# CAN_IB_V1.net
KiCad netlist of a schematic drawn in Altium Designer
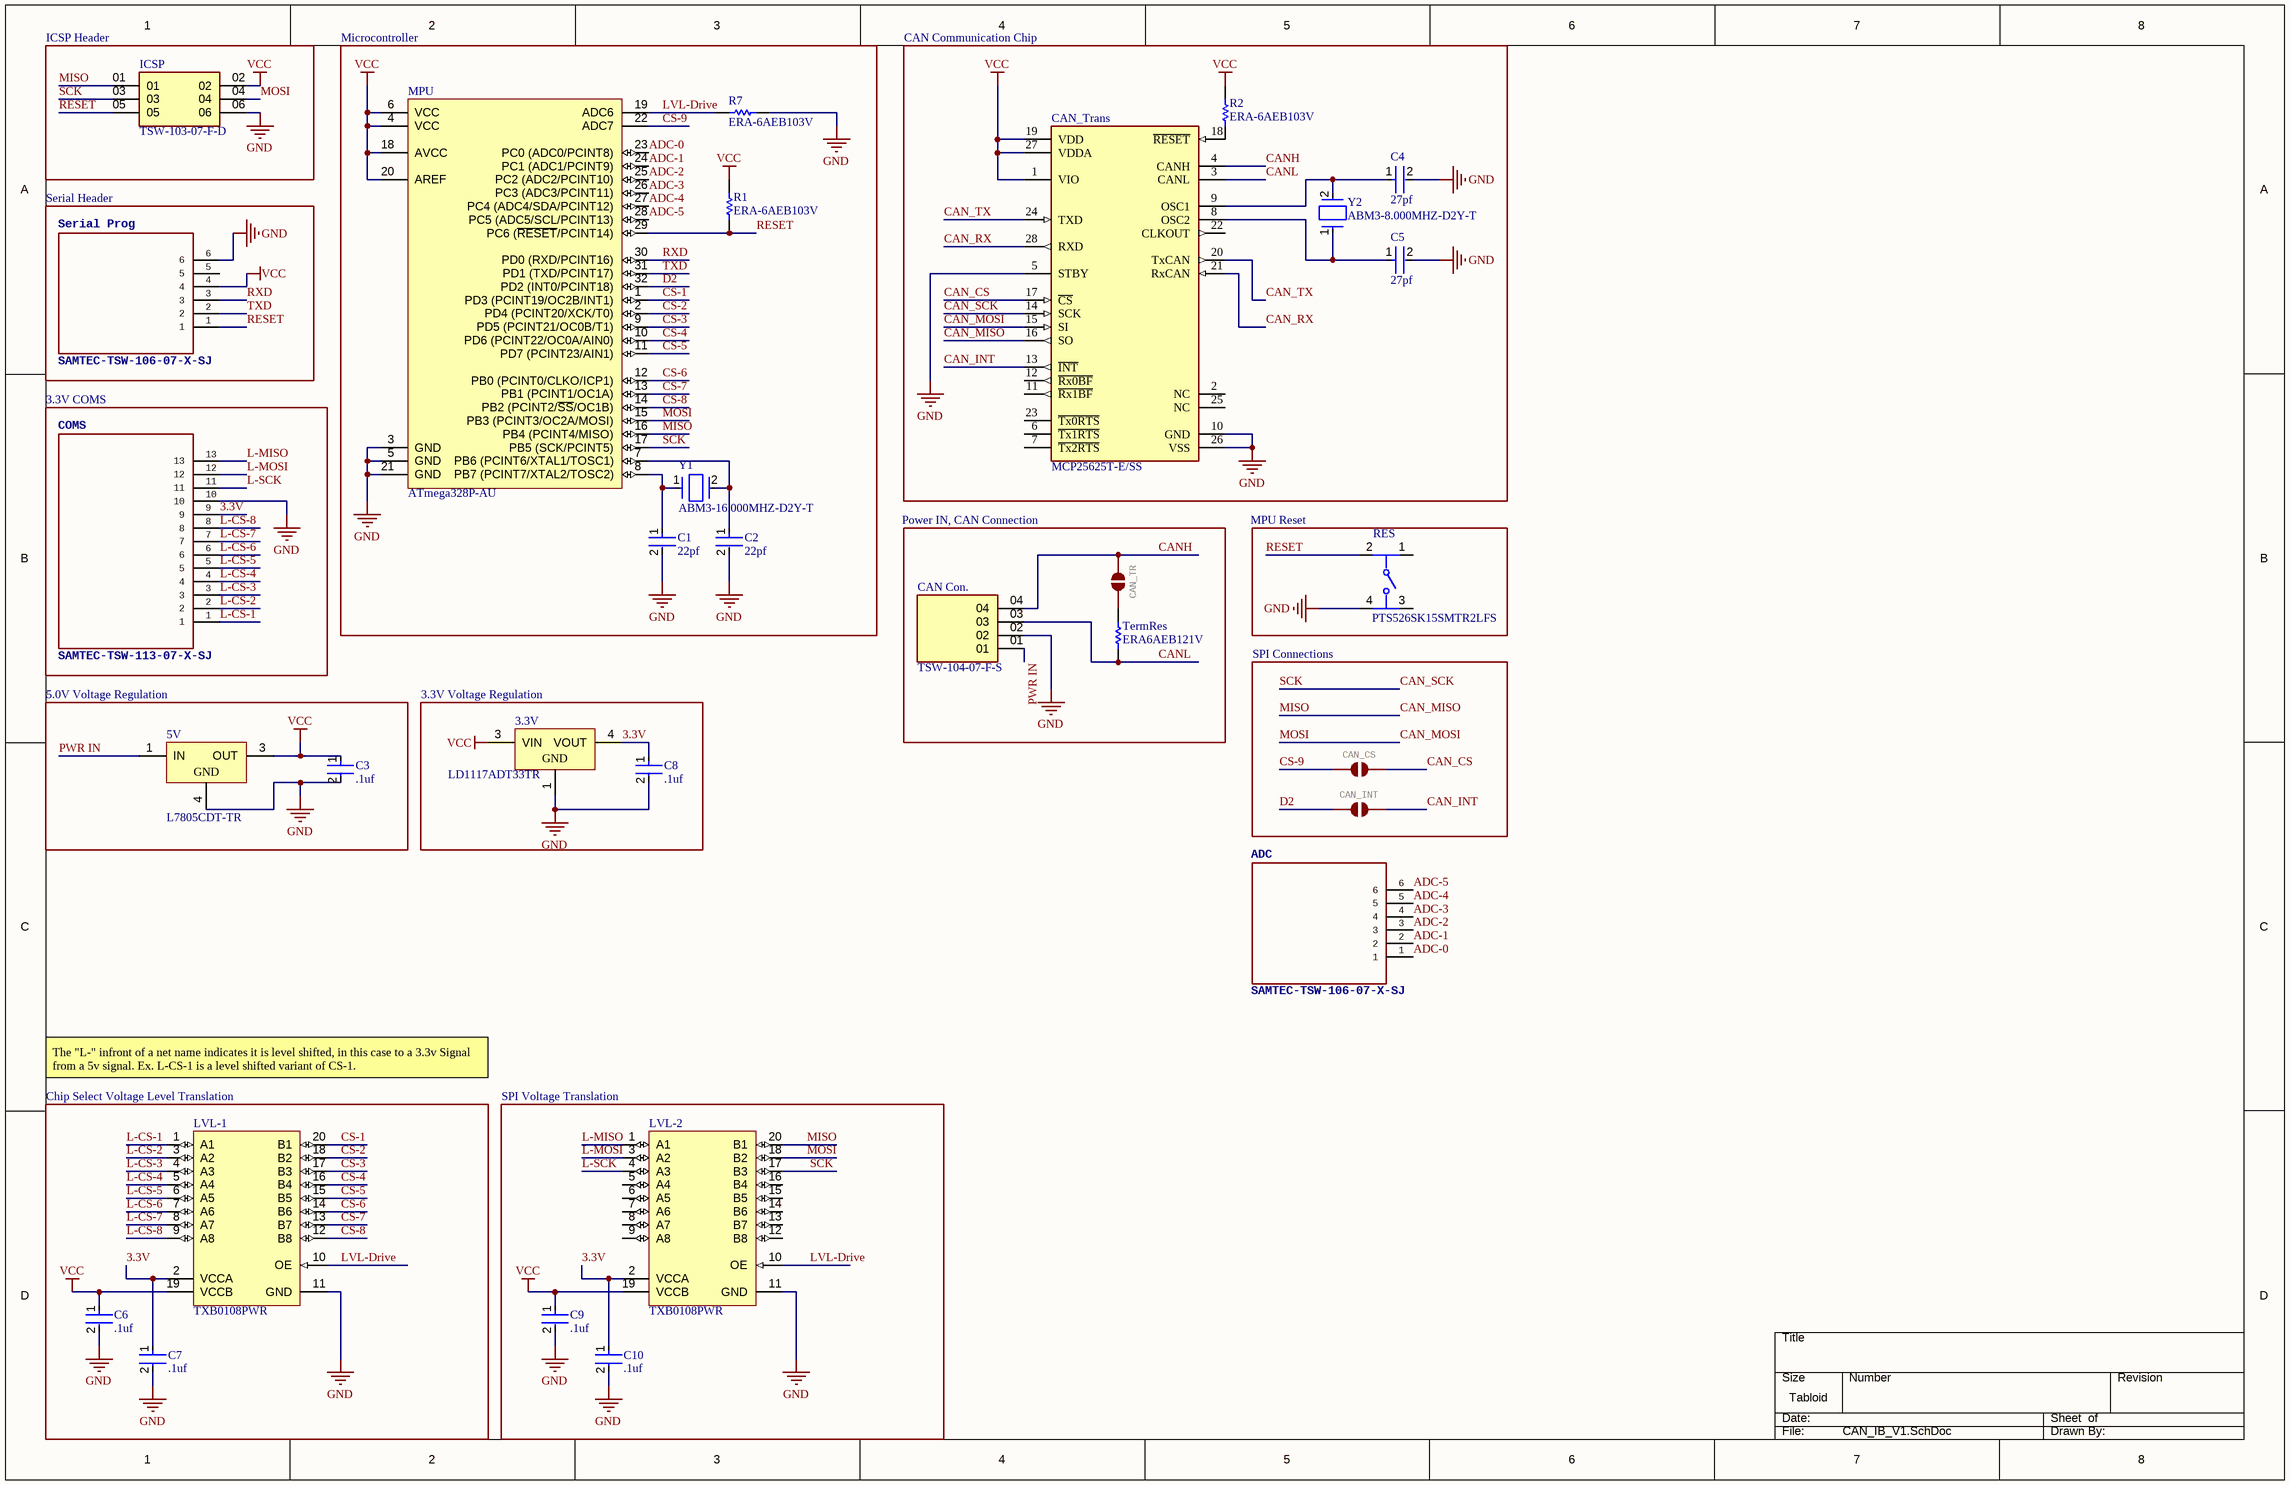
[diagram p0: CAN_IB_V1.SchDoc]

(export (version "E")
  (design (tool "Eeschema 10.0.6"))
  (components
    (comp (ref "3.3V")
      (value "LD1117ADT33TR")
      (footprint "TO-252_L")
      (description "1A, Low Drop Positive Voltage Regulator, 3.3V, 3-Pin DPAK, Tape and Reel")
      (libsource (lib "Altium Content Vault") (part "PM-REG-LD1117-SOT3"))
    )
    (comp (ref "5V")
      (value "L7805CDT-TR")
      (footprint "TO-252_N")
      (description "Positive Voltage Regulator, 3-Pin DPAK, Tape and Reel")
      (libsource (lib "Altium Content Vault") (part "PM-REG-L4940-SOT3"))
    )
    (comp (ref "ADC")
      (value "SAMTEC-TSW-106-07-X-SJ")
      (footprint "SAMTEC-TSW-106-07-X-S")
      (libsource (lib "TSW-106-07-F-S") (part "SAMTEC-TSW-106-07-X-SJ"))
    )
    (comp (ref "C1")
      (value "22pf")
      (footprint "FP-GRM21B-0_15-IPC_C")
      (description "Chip Multilayer Ceramic Capacitors for General Purpose, 0805, 10uF, X5R, 15%, 10%, 25V")
      (fields (field (name "VOLTAGE") "25V") (field (name "TOLERANCE") "10%"))
      (libsource (lib "Altium Content Vault") (part "b4654b650e69147ec39a6b967a45e02"))
    )
    (comp (ref "C2")
      (value "22pf")
      (footprint "FP-GRM21B-0_15-IPC_C")
      (description "Chip Multilayer Ceramic Capacitors for General Purpose, 0805, 10uF, X5R, 15%, 10%, 25V")
      (fields (field (name "VOLTAGE") "25V") (field (name "TOLERANCE") "10%"))
      (libsource (lib "Altium Content Vault") (part "b4654b650e69147ec39a6b967a45e02"))
    )
    (comp (ref "C3")
      (value ".1uf")
      (footprint "FP-GRM21B-0_15-IPC_C")
      (description "Chip Multilayer Ceramic Capacitors for General Purpose, 0805, 10uF, X5R, 15%, 10%, 25V")
      (fields (field (name "VOLTAGE") "25V") (field (name "TOLERANCE") "10%"))
      (libsource (lib "Altium Content Vault") (part "b4654b650e69147ec39a6b967a45e02"))
    )
    (comp (ref "C4")
      (value "27pf")
      (footprint "FP-GRM21B-0_15-IPC_C")
      (description "Chip Multilayer Ceramic Capacitors for General Purpose, 0805, 10uF, X5R, 15%, 10%, 25V")
      (fields (field (name "VOLTAGE") "25V") (field (name "TOLERANCE") "10%"))
      (libsource (lib "Altium Content Vault") (part "b4654b650e69147ec39a6b967a45e02"))
    )
    (comp (ref "C5")
      (value "27pf")
      (footprint "FP-GRM21B-0_15-IPC_C")
      (description "Chip Multilayer Ceramic Capacitors for General Purpose, 0805, 10uF, X5R, 15%, 10%, 25V")
      (fields (field (name "VOLTAGE") "25V") (field (name "TOLERANCE") "10%"))
      (libsource (lib "Altium Content Vault") (part "b4654b650e69147ec39a6b967a45e02"))
    )
    (comp (ref "C6")
      (value ".1uf")
      (footprint "FP-GRM21B-0_15-IPC_C")
      (description "Chip Multilayer Ceramic Capacitors for General Purpose, 0805, 10uF, X5R, 15%, 10%, 25V")
      (fields (field (name "VOLTAGE") "25V") (field (name "TOLERANCE") "10%"))
      (libsource (lib "Altium Content Vault") (part "b4654b650e69147ec39a6b967a45e02"))
    )
    (comp (ref "C7")
      (value ".1uf")
      (footprint "FP-GRM21B-0_15-IPC_C")
      (description "Chip Multilayer Ceramic Capacitors for General Purpose, 0805, 10uF, X5R, 15%, 10%, 25V")
      (fields (field (name "VOLTAGE") "25V") (field (name "TOLERANCE") "10%"))
      (libsource (lib "Altium Content Vault") (part "b4654b650e69147ec39a6b967a45e02"))
    )
    (comp (ref "C8")
      (value ".1uf")
      (footprint "FP-GRM21B-0_15-IPC_C")
      (description "Chip Multilayer Ceramic Capacitors for General Purpose, 0805, 10uF, X5R, 15%, 10%, 25V")
      (fields (field (name "VOLTAGE") "25V") (field (name "TOLERANCE") "10%"))
      (libsource (lib "Altium Content Vault") (part "b4654b650e69147ec39a6b967a45e02"))
    )
    (comp (ref "C9")
      (value ".1uf")
      (footprint "FP-GRM21B-0_15-IPC_C")
      (description "Chip Multilayer Ceramic Capacitors for General Purpose, 0805, 10uF, X5R, 15%, 10%, 25V")
      (fields (field (name "VOLTAGE") "25V") (field (name "TOLERANCE") "10%"))
      (libsource (lib "Altium Content Vault") (part "b4654b650e69147ec39a6b967a45e02"))
    )
    (comp (ref "C10")
      (value ".1uf")
      (footprint "FP-GRM21B-0_15-IPC_C")
      (description "Chip Multilayer Ceramic Capacitors for General Purpose, 0805, 10uF, X5R, 15%, 10%, 25V")
      (fields (field (name "VOLTAGE") "25V") (field (name "TOLERANCE") "10%"))
      (libsource (lib "Altium Content Vault") (part "b4654b650e69147ec39a6b967a45e02"))
    )
    (comp (ref "CAN Con.")
      (value "TSW-104-07-F-S")
      (footprint "SAMTEC_TSW-104-07-F-S")
      (fields (field (name "MF") "Samtec"))
      (libsource (lib "TSW-104-07-F-S") (part "TSW-104-07-F-S"))
    )
    (comp (ref "CAN_CS")
      (value "~")
      (footprint "SMT-JUMPER_2_NO_SILK")
      (libsource (lib "SparkFun-Jumpers.Library") (part "JUMPER-SMT_2_NO_SILK"))
    )
    (comp (ref "CAN_INT")
      (value "~")
      (footprint "SMT-JUMPER_2_NO_SILK")
      (libsource (lib "SparkFun-Jumpers.Library") (part "JUMPER-SMT_2_NO_SILK"))
    )
    (comp (ref "CAN_TR")
      (value "~")
      (footprint "SMT-JUMPER_2_NO_SILK")
      (libsource (lib "SparkFun-Jumpers.Library") (part "JUMPER-SMT_2_NO_SILK"))
    )
    (comp (ref "CAN_Trans")
      (value "MCP25625T-E/SS")
      (footprint "FP-C04-073-IPC_B")
      (description "IC TRANSCEIVER 1/1 28SSOP")
      (libsource (lib "Altium Content Vault") (part "1eb43db0d86e80dbea2ef2edec005e1"))
    )
    (comp (ref "COMS")
      (value "SAMTEC-TSW-113-07-X-SJ")
      (footprint "SAMTEC-TSW-113-07-X-S")
      (libsource (lib "SAMTEC-TSW-113-07-X-S") (part "SAMTEC-TSW-113-07-X-SJ"))
    )
    (comp (ref "ICSP")
      (value "TSW-103-07-F-D")
      (footprint "SAMTEC_TSW-103-07-F-D")
      (fields (field (name "MF") "Samtec"))
      (libsource (lib "TSW-103-07-F-D") (part "TSW-103-07-F-D"))
    )
    (comp (ref "LVL-1")
      (value "TXB0108PWR")
      (footprint "PW0020A_L")
      (fields (field (name "MANUFACTURER") "Texas Instruments"))
      (libsource (lib "Altium Content Vault") (part "TI-TXB0108-PW-20"))
    )
    (comp (ref "LVL-2")
      (value "TXB0108PWR")
      (footprint "PW0020A_L")
      (fields (field (name "MANUFACTURER") "Texas Instruments"))
      (libsource (lib "Altium Content Vault") (part "TI-TXB0108-PW-20"))
    )
    (comp (ref "MPU")
      (value "ATmega328P-AU")
      (footprint "32A_M")
      (libsource (lib "Altium Content Vault") (part "MC-8B-ATM48-SQ32"))
    )
    (comp (ref "R1")
      (value "ERA-6AEB103V")
      (footprint "RESC2013X60X40LL20T25_A")
      (fields (field (name "TOLERANCE") "0.1%") (field (name "MANUFACTURER") "Panasonic"))
      (libsource (lib "Altium Content Vault") (part "RES-2"))
    )
    (comp (ref "R2")
      (value "ERA-6AEB103V")
      (footprint "RESC2013X60X40LL20T25_A")
      (fields (field (name "TOLERANCE") "0.1%") (field (name "MANUFACTURER") "Panasonic"))
      (libsource (lib "Altium Content Vault") (part "RES-2"))
    )
    (comp (ref "R7")
      (value "ERA-6AEB103V")
      (footprint "RESC2013X60X40LL20T25_A")
      (fields (field (name "TOLERANCE") "0.1%") (field (name "MANUFACTURER") "Panasonic"))
      (libsource (lib "Altium Content Vault") (part "RES-2"))
    )
    (comp (ref "RES")
      (value "PTS526SK15SMTR2LFS")
      (footprint "FP-PTS526SK15SMTR2LFS-MFG")
      (description "TACT 5.2 X 5.2, 1.5 MM H, 260GF,")
      (fields
        (field (name "MANUFACTURER") "C&K")
        (field (name "OCTOPART") "https://octopart.com/pts526+sk15+smtr2+lfs-c%26k+components-100617999")
      )
      (libsource (lib "Altium Content Vault") (part "b8895f3f4cefb76e1819d2863dba89b"))
    )
    (comp (ref "Serial Prog")
      (value "SAMTEC-TSW-106-07-X-SJ")
      (footprint "SAMTEC-TSW-106-07-X-S")
      (libsource (lib "TSW-106-07-F-S") (part "SAMTEC-TSW-106-07-X-SJ"))
    )
    (comp (ref "TermRes")
      (value "ERA6AEB121V")
      (footprint "RESC2013X60X40ML20T25")
      (fields (field (name "MANUFACTURER") "Panasonic"))
      (libsource (lib "Altium Content Vault") (part "RES"))
    )
    (comp (ref "Y1")
      (value "ABM3-16.000MHZ-D2Y-T")
      (footprint "FP-ABM3-MFG")
      (description "Crystal 16MHz ±20ppm 18pF SMD-2 5mm x 3.2mm")
      (fields (field (name "TOLERANCE") "20ppm"))
      (libsource (lib "Altium Content Vault") (part "c23a69dc6c9e2f18f2079038eb95dd1"))
    )
    (comp (ref "Y2")
      (value "ABM3-8.000MHZ-D2Y-T")
      (footprint "FP-ABM3-MFG")
      (description "Crystal 8MHz ±20ppm 18pF SMD-2 5mm x 3.2mm")
      (fields (field (name "TOLERANCE") "20ppm"))
      (libsource (lib "Altium Content Vault") (part "c23a69dc6c9e2f18f2079038eb95dd1"))
    )
  )
  (nets
    (net (code "1") (name "/3.3V") (class "Default")
      (node (ref "3.3V") (pin "4") (pinfunction "VOUT_4") (pintype "power_in"))
      (node (ref "C10") (pin "1") (pinfunction "1_1") (pintype "passive"))
      (node (ref "C7") (pin "1") (pinfunction "1_1") (pintype "passive"))
      (node (ref "C8") (pin "1") (pinfunction "1_1") (pintype "passive"))
      (node (ref "COMS") (pin "9") (pinfunction "9_9") (pintype "passive"))
      (node (ref "LVL-1") (pin "2") (pinfunction "VCCA_2") (pintype "power_in"))
      (node (ref "LVL-2") (pin "2") (pinfunction "VCCA_2") (pintype "power_in"))
    )
    (net (code "2") (name "/ADC-0") (class "Default")
      (node (ref "ADC") (pin "1") (pinfunction "1_1") (pintype "passive"))
      (node (ref "MPU") (pin "23") (pinfunction "PC0_(ADC0/PCINT8)_23") (pintype "bidirectional"))
    )
    (net (code "3") (name "/ADC-1") (class "Default")
      (node (ref "ADC") (pin "2") (pinfunction "2_2") (pintype "passive"))
      (node (ref "MPU") (pin "24") (pinfunction "PC1_(ADC1/PCINT9)_24") (pintype "bidirectional"))
    )
    (net (code "4") (name "/ADC-2") (class "Default")
      (node (ref "ADC") (pin "3") (pinfunction "3_3") (pintype "passive"))
      (node (ref "MPU") (pin "25") (pinfunction "PC2_(ADC2/PCINT10)_25") (pintype "bidirectional"))
    )
    (net (code "5") (name "/ADC-3") (class "Default")
      (node (ref "ADC") (pin "4") (pinfunction "4_4") (pintype "passive"))
      (node (ref "MPU") (pin "26") (pinfunction "PC3_(ADC3/PCINT11)_26") (pintype "bidirectional"))
    )
    (net (code "6") (name "/ADC-4") (class "Default")
      (node (ref "ADC") (pin "5") (pinfunction "5_5") (pintype "passive"))
      (node (ref "MPU") (pin "27") (pinfunction "PC4_(ADC4/SDA/PCINT12)_27") (pintype "bidirectional"))
    )
    (net (code "7") (name "/ADC-5") (class "Default")
      (node (ref "ADC") (pin "6") (pinfunction "6_6") (pintype "passive"))
      (node (ref "MPU") (pin "28") (pinfunction "PC5_(ADC5/SCL/PCINT13)_28") (pintype "bidirectional"))
    )
    (net (code "8") (name "/CANH") (class "Default")
      (node (ref "CAN Con.") (pin "04") (pinfunction "04_04") (pintype "passive"))
      (node (ref "CAN_TR") (pin "1") (pinfunction "1_1") (pintype "passive"))
      (node (ref "CAN_Trans") (pin "4") (pinfunction "CANH_4") (pintype "passive"))
    )
    (net (code "9") (name "/CANL") (class "Default")
      (node (ref "CAN Con.") (pin "03") (pinfunction "03_03") (pintype "passive"))
      (node (ref "CAN_Trans") (pin "3") (pinfunction "CANL_3") (pintype "passive"))
      (node (ref "TermRes") (pin "1") (pinfunction "1_1") (pintype "passive"))
    )
    (net (code "10") (name "/CAN_CS") (class "Default")
      (node (ref "CAN_CS") (pin "2") (pinfunction "2_2") (pintype "passive"))
      (node (ref "CAN_Trans") (pin "17") (pinfunction "~{CS}_17") (pintype "input"))
    )
    (net (code "11") (name "/CAN_INT") (class "Default")
      (node (ref "CAN_INT") (pin "2") (pinfunction "2_2") (pintype "passive"))
      (node (ref "CAN_Trans") (pin "13") (pinfunction "~{INT}_13") (pintype "output"))
    )
    (net (code "12") (name "/CAN_MISO") (class "Default")
      (node (ref "CAN_Trans") (pin "16") (pinfunction "SO_16") (pintype "output"))
      (node (ref "ICSP") (pin "01") (pinfunction "01_01") (pintype "passive"))
      (node (ref "LVL-2") (pin "20") (pinfunction "B1_20") (pintype "bidirectional"))
      (node (ref "MPU") (pin "16") (pinfunction "PB4_(PCINT4/MISO)_16") (pintype "bidirectional"))
    )
    (net (code "13") (name "/CAN_MOSI") (class "Default")
      (node (ref "CAN_Trans") (pin "15") (pinfunction "SI_15") (pintype "input"))
      (node (ref "ICSP") (pin "04") (pinfunction "04_04") (pintype "passive"))
      (node (ref "LVL-2") (pin "18") (pinfunction "B2_18") (pintype "bidirectional"))
      (node (ref "MPU") (pin "15") (pinfunction "PB3_(PCINT3/OC2A/MOSI)_15") (pintype "bidirectional"))
    )
    (net (code "14") (name "/CAN_RX") (class "Default")
      (node (ref "CAN_Trans") (pin "21") (pinfunction "RxCAN_21") (pintype "input"))
      (node (ref "CAN_Trans") (pin "28") (pinfunction "RXD_28") (pintype "output"))
    )
    (net (code "15") (name "/CAN_SCK") (class "Default")
      (node (ref "CAN_Trans") (pin "14") (pinfunction "SCK_14") (pintype "input"))
      (node (ref "ICSP") (pin "03") (pinfunction "03_03") (pintype "passive"))
      (node (ref "LVL-2") (pin "17") (pinfunction "B3_17") (pintype "bidirectional"))
      (node (ref "MPU") (pin "17") (pinfunction "PB5_(SCK/PCINT5)_17") (pintype "bidirectional"))
    )
    (net (code "16") (name "/CAN_TX") (class "Default")
      (node (ref "CAN_Trans") (pin "20") (pinfunction "TxCAN_20") (pintype "output"))
      (node (ref "CAN_Trans") (pin "24") (pinfunction "TXD_24") (pintype "input"))
    )
    (net (code "17") (name "/CS-1") (class "Default")
      (node (ref "LVL-1") (pin "20") (pinfunction "B1_20") (pintype "bidirectional"))
      (node (ref "MPU") (pin "1") (pinfunction "PD3_(PCINT19/OC2B/INT1)_1") (pintype "bidirectional"))
    )
    (net (code "18") (name "/CS-2") (class "Default")
      (node (ref "LVL-1") (pin "18") (pinfunction "B2_18") (pintype "bidirectional"))
      (node (ref "MPU") (pin "2") (pinfunction "PD4_(PCINT20/XCK/T0)_2") (pintype "bidirectional"))
    )
    (net (code "19") (name "/CS-3") (class "Default")
      (node (ref "LVL-1") (pin "17") (pinfunction "B3_17") (pintype "bidirectional"))
      (node (ref "MPU") (pin "9") (pinfunction "PD5_(PCINT21/OC0B/T1)_9") (pintype "bidirectional"))
    )
    (net (code "20") (name "/CS-4") (class "Default")
      (node (ref "LVL-1") (pin "16") (pinfunction "B4_16") (pintype "bidirectional"))
      (node (ref "MPU") (pin "10") (pinfunction "PD6_(PCINT22/OC0A/AIN0)_10") (pintype "bidirectional"))
    )
    (net (code "21") (name "/CS-5") (class "Default")
      (node (ref "LVL-1") (pin "15") (pinfunction "B5_15") (pintype "bidirectional"))
      (node (ref "MPU") (pin "11") (pinfunction "PD7_(PCINT23/AIN1)_11") (pintype "bidirectional"))
    )
    (net (code "22") (name "/CS-6") (class "Default")
      (node (ref "LVL-1") (pin "14") (pinfunction "B6_14") (pintype "bidirectional"))
      (node (ref "MPU") (pin "12") (pinfunction "PB0_(PCINT0/CLKO/ICP1)_12") (pintype "bidirectional"))
    )
    (net (code "23") (name "/CS-7") (class "Default")
      (node (ref "LVL-1") (pin "13") (pinfunction "B7_13") (pintype "bidirectional"))
      (node (ref "MPU") (pin "13") (pinfunction "PB1_(PCINT1/OC1A)_13") (pintype "bidirectional"))
    )
    (net (code "24") (name "/CS-8") (class "Default")
      (node (ref "LVL-1") (pin "12") (pinfunction "B8_12") (pintype "bidirectional"))
      (node (ref "MPU") (pin "14") (pinfunction "PB2_(PCINT2/~{SS}/OC1B)_14") (pintype "bidirectional"))
    )
    (net (code "25") (name "/CS-9") (class "Default")
      (node (ref "CAN_CS") (pin "1") (pinfunction "1_1") (pintype "passive"))
      (node (ref "MPU") (pin "22") (pinfunction "ADC7_22") (pintype "passive"))
    )
    (net (code "26") (name "/D2") (class "Default")
      (node (ref "CAN_INT") (pin "1") (pinfunction "1_1") (pintype "passive"))
      (node (ref "MPU") (pin "32") (pinfunction "PD2_(INT0/PCINT18)_32") (pintype "bidirectional"))
    )
    (net (code "27") (name "/L-CS-1") (class "Default")
      (node (ref "COMS") (pin "1") (pinfunction "1_1") (pintype "passive"))
      (node (ref "LVL-1") (pin "1") (pinfunction "A1_1") (pintype "bidirectional"))
    )
    (net (code "28") (name "/L-CS-2") (class "Default")
      (node (ref "COMS") (pin "2") (pinfunction "2_2") (pintype "passive"))
      (node (ref "LVL-1") (pin "3") (pinfunction "A2_3") (pintype "bidirectional"))
    )
    (net (code "29") (name "/L-CS-3") (class "Default")
      (node (ref "COMS") (pin "3") (pinfunction "3_3") (pintype "passive"))
      (node (ref "LVL-1") (pin "4") (pinfunction "A3_4") (pintype "bidirectional"))
    )
    (net (code "30") (name "/L-CS-4") (class "Default")
      (node (ref "COMS") (pin "4") (pinfunction "4_4") (pintype "passive"))
      (node (ref "LVL-1") (pin "5") (pinfunction "A4_5") (pintype "bidirectional"))
    )
    (net (code "31") (name "/L-CS-5") (class "Default")
      (node (ref "COMS") (pin "5") (pinfunction "5_5") (pintype "passive"))
      (node (ref "LVL-1") (pin "6") (pinfunction "A5_6") (pintype "bidirectional"))
    )
    (net (code "32") (name "/L-CS-6") (class "Default")
      (node (ref "COMS") (pin "6") (pinfunction "6_6") (pintype "passive"))
      (node (ref "LVL-1") (pin "7") (pinfunction "A6_7") (pintype "bidirectional"))
    )
    (net (code "33") (name "/L-CS-7") (class "Default")
      (node (ref "COMS") (pin "7") (pinfunction "7_7") (pintype "passive"))
      (node (ref "LVL-1") (pin "8") (pinfunction "A7_8") (pintype "bidirectional"))
    )
    (net (code "34") (name "/L-CS-8") (class "Default")
      (node (ref "COMS") (pin "8") (pinfunction "8_8") (pintype "passive"))
      (node (ref "LVL-1") (pin "9") (pinfunction "A8_9") (pintype "bidirectional"))
    )
    (net (code "35") (name "/L-MISO") (class "Default")
      (node (ref "COMS") (pin "13") (pinfunction "13_13") (pintype "passive"))
      (node (ref "LVL-2") (pin "1") (pinfunction "A1_1") (pintype "bidirectional"))
    )
    (net (code "36") (name "/L-MOSI") (class "Default")
      (node (ref "COMS") (pin "12") (pinfunction "12_12") (pintype "passive"))
      (node (ref "LVL-2") (pin "3") (pinfunction "A2_3") (pintype "bidirectional"))
    )
    (net (code "37") (name "/L-SCK") (class "Default")
      (node (ref "COMS") (pin "11") (pinfunction "11_11") (pintype "passive"))
      (node (ref "LVL-2") (pin "4") (pinfunction "A3_4") (pintype "bidirectional"))
    )
    (net (code "38") (name "/LVL-Drive") (class "Default")
      (node (ref "LVL-1") (pin "10") (pinfunction "OE_10") (pintype "input"))
      (node (ref "LVL-2") (pin "10") (pinfunction "OE_10") (pintype "input"))
      (node (ref "MPU") (pin "19") (pinfunction "ADC6_19") (pintype "passive"))
      (node (ref "R7") (pin "1") (pinfunction "1_1") (pintype "passive"))
    )
    (net (code "39") (name "/PWR IN") (class "Default")
      (node (ref "5V") (pin "1") (pinfunction "IN_1") (pintype "power_in"))
      (node (ref "CAN Con.") (pin "01") (pinfunction "01_01") (pintype "passive"))
    )
    (net (code "40") (name "/RESET") (class "Default")
      (node (ref "ICSP") (pin "05") (pinfunction "05_05") (pintype "passive"))
      (node (ref "MPU") (pin "29") (pinfunction "PC6_(~{RESET}/PCINT14)_29") (pintype "bidirectional"))
      (node (ref "R1") (pin "1") (pinfunction "1_1") (pintype "passive"))
      (node (ref "RES") (pin "2") (pinfunction "2_2") (pintype "passive"))
      (node (ref "Serial Prog") (pin "1") (pinfunction "1_1") (pintype "passive"))
    )
    (net (code "41") (name "/RXD") (class "Default")
      (node (ref "MPU") (pin "30") (pinfunction "PD0_(RXD/PCINT16)_30") (pintype "bidirectional"))
      (node (ref "Serial Prog") (pin "3") (pinfunction "3_3") (pintype "passive"))
    )
    (net (code "42") (name "/TXD") (class "Default")
      (node (ref "MPU") (pin "31") (pinfunction "PD1_(TXD/PCINT17)_31") (pintype "bidirectional"))
      (node (ref "Serial Prog") (pin "2") (pinfunction "2_2") (pintype "passive"))
    )
    (net (code "43") (name "GND") (class "Default")
      (node (ref "3.3V") (pin "1") (pinfunction "GND_1") (pintype "power_in"))
      (node (ref "5V") (pin "4") (pinfunction "GND_4") (pintype "power_in"))
      (node (ref "C1") (pin "2") (pinfunction "2_2") (pintype "passive"))
      (node (ref "C10") (pin "2") (pinfunction "2_2") (pintype "passive"))
      (node (ref "C2") (pin "2") (pinfunction "2_2") (pintype "passive"))
      (node (ref "C3") (pin "2") (pinfunction "2_2") (pintype "passive"))
      (node (ref "C4") (pin "2") (pinfunction "2_2") (pintype "passive"))
      (node (ref "C5") (pin "2") (pinfunction "2_2") (pintype "passive"))
      (node (ref "C6") (pin "2") (pinfunction "2_2") (pintype "passive"))
      (node (ref "C7") (pin "2") (pinfunction "2_2") (pintype "passive"))
      (node (ref "C8") (pin "2") (pinfunction "2_2") (pintype "passive"))
      (node (ref "C9") (pin "2") (pinfunction "2_2") (pintype "passive"))
      (node (ref "CAN Con.") (pin "02") (pinfunction "02_02") (pintype "passive"))
      (node (ref "CAN_Trans") (pin "10") (pinfunction "GND_10") (pintype "power_in"))
      (node (ref "CAN_Trans") (pin "26") (pinfunction "VSS_26") (pintype "power_in"))
      (node (ref "CAN_Trans") (pin "5") (pinfunction "STBY_5") (pintype "passive"))
      (node (ref "COMS") (pin "10") (pinfunction "10_10") (pintype "passive"))
      (node (ref "ICSP") (pin "06") (pinfunction "06_06") (pintype "passive"))
      (node (ref "LVL-1") (pin "11") (pinfunction "GND_11") (pintype "power_in"))
      (node (ref "LVL-2") (pin "11") (pinfunction "GND_11") (pintype "power_in"))
      (node (ref "MPU") (pin "21") (pinfunction "GND_21") (pintype "power_in"))
      (node (ref "MPU") (pin "3") (pinfunction "GND_3") (pintype "power_in"))
      (node (ref "MPU") (pin "5") (pinfunction "GND_5") (pintype "power_in"))
      (node (ref "R7") (pin "2") (pinfunction "2_2") (pintype "passive"))
      (node (ref "RES") (pin "4") (pinfunction "4_4") (pintype "passive"))
      (node (ref "Serial Prog") (pin "6") (pinfunction "6_6") (pintype "passive"))
    )
    (net (code "44") (name "Net-(CAN_TR-Pad2)") (class "Default")
      (node (ref "CAN_TR") (pin "2") (pinfunction "2_2") (pintype "passive"))
      (node (ref "TermRes") (pin "2") (pinfunction "2_2") (pintype "passive"))
    )
    (net (code "45") (name "Net-(CAN_Trans-OSC1)") (class "Default")
      (node (ref "C4") (pin "1") (pinfunction "1_1") (pintype "passive"))
      (node (ref "CAN_Trans") (pin "9") (pinfunction "OSC1_9") (pintype "passive"))
      (node (ref "Y2") (pin "2") (pinfunction "2_2") (pintype "passive"))
    )
    (net (code "46") (name "Net-(CAN_Trans-OSC2)") (class "Default")
      (node (ref "C5") (pin "1") (pinfunction "1_1") (pintype "passive"))
      (node (ref "CAN_Trans") (pin "8") (pinfunction "OSC2_8") (pintype "passive"))
      (node (ref "Y2") (pin "1") (pinfunction "1_1") (pintype "passive"))
    )
    (net (code "47") (name "Net-(CAN_Trans-~{RESET})") (class "Default")
      (node (ref "CAN_Trans") (pin "18") (pinfunction "~{RESET}_18") (pintype "input"))
      (node (ref "R2") (pin "1") (pinfunction "1_1") (pintype "passive"))
    )
    (net (code "48") (name "Net-(MPU-PB6_(PCINT6{slash}XTAL1{slash}TOSC1))") (class "Default")
      (node (ref "C2") (pin "1") (pinfunction "1_1") (pintype "passive"))
      (node (ref "MPU") (pin "7") (pinfunction "PB6_(PCINT6/XTAL1/TOSC1)_7") (pintype "bidirectional"))
      (node (ref "Y1") (pin "2") (pinfunction "2_2") (pintype "passive"))
    )
    (net (code "49") (name "Net-(MPU-PB7_(PCINT7{slash}XTAL2{slash}TOSC2))") (class "Default")
      (node (ref "C1") (pin "1") (pinfunction "1_1") (pintype "passive"))
      (node (ref "MPU") (pin "8") (pinfunction "PB7_(PCINT7/XTAL2/TOSC2)_8") (pintype "bidirectional"))
      (node (ref "Y1") (pin "1") (pinfunction "1_1") (pintype "passive"))
    )
    (net (code "50") (name "VCC") (class "Default")
      (node (ref "3.3V") (pin "3") (pinfunction "VIN_3") (pintype "power_in"))
      (node (ref "5V") (pin "3") (pinfunction "OUT_3") (pintype "power_in"))
      (node (ref "C3") (pin "1") (pinfunction "1_1") (pintype "passive"))
      (node (ref "C6") (pin "1") (pinfunction "1_1") (pintype "passive"))
      (node (ref "C9") (pin "1") (pinfunction "1_1") (pintype "passive"))
      (node (ref "CAN_Trans") (pin "1") (pinfunction "VIO_1") (pintype "power_in"))
      (node (ref "CAN_Trans") (pin "19") (pinfunction "VDD_19") (pintype "power_in"))
      (node (ref "CAN_Trans") (pin "27") (pinfunction "VDDA_27") (pintype "power_in"))
      (node (ref "ICSP") (pin "02") (pinfunction "02_02") (pintype "passive"))
      (node (ref "LVL-1") (pin "19") (pinfunction "VCCB_19") (pintype "power_in"))
      (node (ref "LVL-2") (pin "19") (pinfunction "VCCB_19") (pintype "power_in"))
      (node (ref "MPU") (pin "18") (pinfunction "AVCC_18") (pintype "power_in"))
      (node (ref "MPU") (pin "20") (pinfunction "AREF_20") (pintype "passive"))
      (node (ref "MPU") (pin "4") (pinfunction "VCC_4") (pintype "power_in"))
      (node (ref "MPU") (pin "6") (pinfunction "VCC_6") (pintype "power_in"))
      (node (ref "R1") (pin "2") (pinfunction "2_2") (pintype "passive"))
      (node (ref "R2") (pin "2") (pinfunction "2_2") (pintype "passive"))
      (node (ref "Serial Prog") (pin "4") (pinfunction "4_4") (pintype "passive"))
    )
    (net (code "51") (name "unconnected-(CAN_Trans-CLKOUT-Pad22)") (class "Default")
      (node (ref "CAN_Trans") (pin "22") (pinfunction "CLKOUT_22") (pintype "output"))
    )
    (net (code "52") (name "unconnected-(CAN_Trans-NC-Pad2)") (class "Default")
      (node (ref "CAN_Trans") (pin "2") (pinfunction "NC_2") (pintype "passive"))
    )
    (net (code "53") (name "unconnected-(CAN_Trans-NC-Pad25)") (class "Default")
      (node (ref "CAN_Trans") (pin "25") (pinfunction "NC_25") (pintype "passive"))
    )
    (net (code "54") (name "unconnected-(CAN_Trans-~{Rx0BF}-Pad12)") (class "Default")
      (node (ref "CAN_Trans") (pin "12") (pinfunction "~{Rx0BF}_12") (pintype "output"))
    )
    (net (code "55") (name "unconnected-(CAN_Trans-~{Rx1BF}-Pad11)") (class "Default")
      (node (ref "CAN_Trans") (pin "11") (pinfunction "~{Rx1BF}_11") (pintype "output"))
    )
    (net (code "56") (name "unconnected-(CAN_Trans-~{Tx0RTS}-Pad23)") (class "Default")
      (node (ref "CAN_Trans") (pin "23") (pinfunction "~{Tx0RTS}_23") (pintype "passive"))
    )
    (net (code "57") (name "unconnected-(CAN_Trans-~{Tx1RTS}-Pad6)") (class "Default")
      (node (ref "CAN_Trans") (pin "6") (pinfunction "~{Tx1RTS}_6") (pintype "passive"))
    )
    (net (code "58") (name "unconnected-(CAN_Trans-~{Tx2RTS}-Pad7)") (class "Default")
      (node (ref "CAN_Trans") (pin "7") (pinfunction "~{Tx2RTS}_7") (pintype "passive"))
    )
    (net (code "59") (name "unconnected-(LVL-2-A4-Pad5)") (class "Default")
      (node (ref "LVL-2") (pin "5") (pinfunction "A4_5") (pintype "bidirectional"))
    )
    (net (code "60") (name "unconnected-(LVL-2-A5-Pad6)") (class "Default")
      (node (ref "LVL-2") (pin "6") (pinfunction "A5_6") (pintype "bidirectional"))
    )
    (net (code "61") (name "unconnected-(LVL-2-A6-Pad7)") (class "Default")
      (node (ref "LVL-2") (pin "7") (pinfunction "A6_7") (pintype "bidirectional"))
    )
    (net (code "62") (name "unconnected-(LVL-2-A7-Pad8)") (class "Default")
      (node (ref "LVL-2") (pin "8") (pinfunction "A7_8") (pintype "bidirectional"))
    )
    (net (code "63") (name "unconnected-(LVL-2-A8-Pad9)") (class "Default")
      (node (ref "LVL-2") (pin "9") (pinfunction "A8_9") (pintype "bidirectional"))
    )
    (net (code "64") (name "unconnected-(LVL-2-B4-Pad16)") (class "Default")
      (node (ref "LVL-2") (pin "16") (pinfunction "B4_16") (pintype "bidirectional"))
    )
    (net (code "65") (name "unconnected-(LVL-2-B5-Pad15)") (class "Default")
      (node (ref "LVL-2") (pin "15") (pinfunction "B5_15") (pintype "bidirectional"))
    )
    (net (code "66") (name "unconnected-(LVL-2-B6-Pad14)") (class "Default")
      (node (ref "LVL-2") (pin "14") (pinfunction "B6_14") (pintype "bidirectional"))
    )
    (net (code "67") (name "unconnected-(LVL-2-B7-Pad13)") (class "Default")
      (node (ref "LVL-2") (pin "13") (pinfunction "B7_13") (pintype "bidirectional"))
    )
    (net (code "68") (name "unconnected-(LVL-2-B8-Pad12)") (class "Default")
      (node (ref "LVL-2") (pin "12") (pinfunction "B8_12") (pintype "bidirectional"))
    )
    (net (code "69") (name "unconnected-(RES-Pad1)") (class "Default")
      (node (ref "RES") (pin "1") (pinfunction "1_1") (pintype "passive"))
    )
    (net (code "70") (name "unconnected-(RES-Pad3)") (class "Default")
      (node (ref "RES") (pin "3") (pinfunction "3_3") (pintype "passive"))
    )
    (net (code "71") (name "unconnected-(Serial Prog-Pad5)") (class "Default")
      (node (ref "Serial Prog") (pin "5") (pinfunction "5_5") (pintype "passive"))
    )
  )
)
